# 09_Misc.net
KiCad netlist of a schematic drawn in Altium Designer
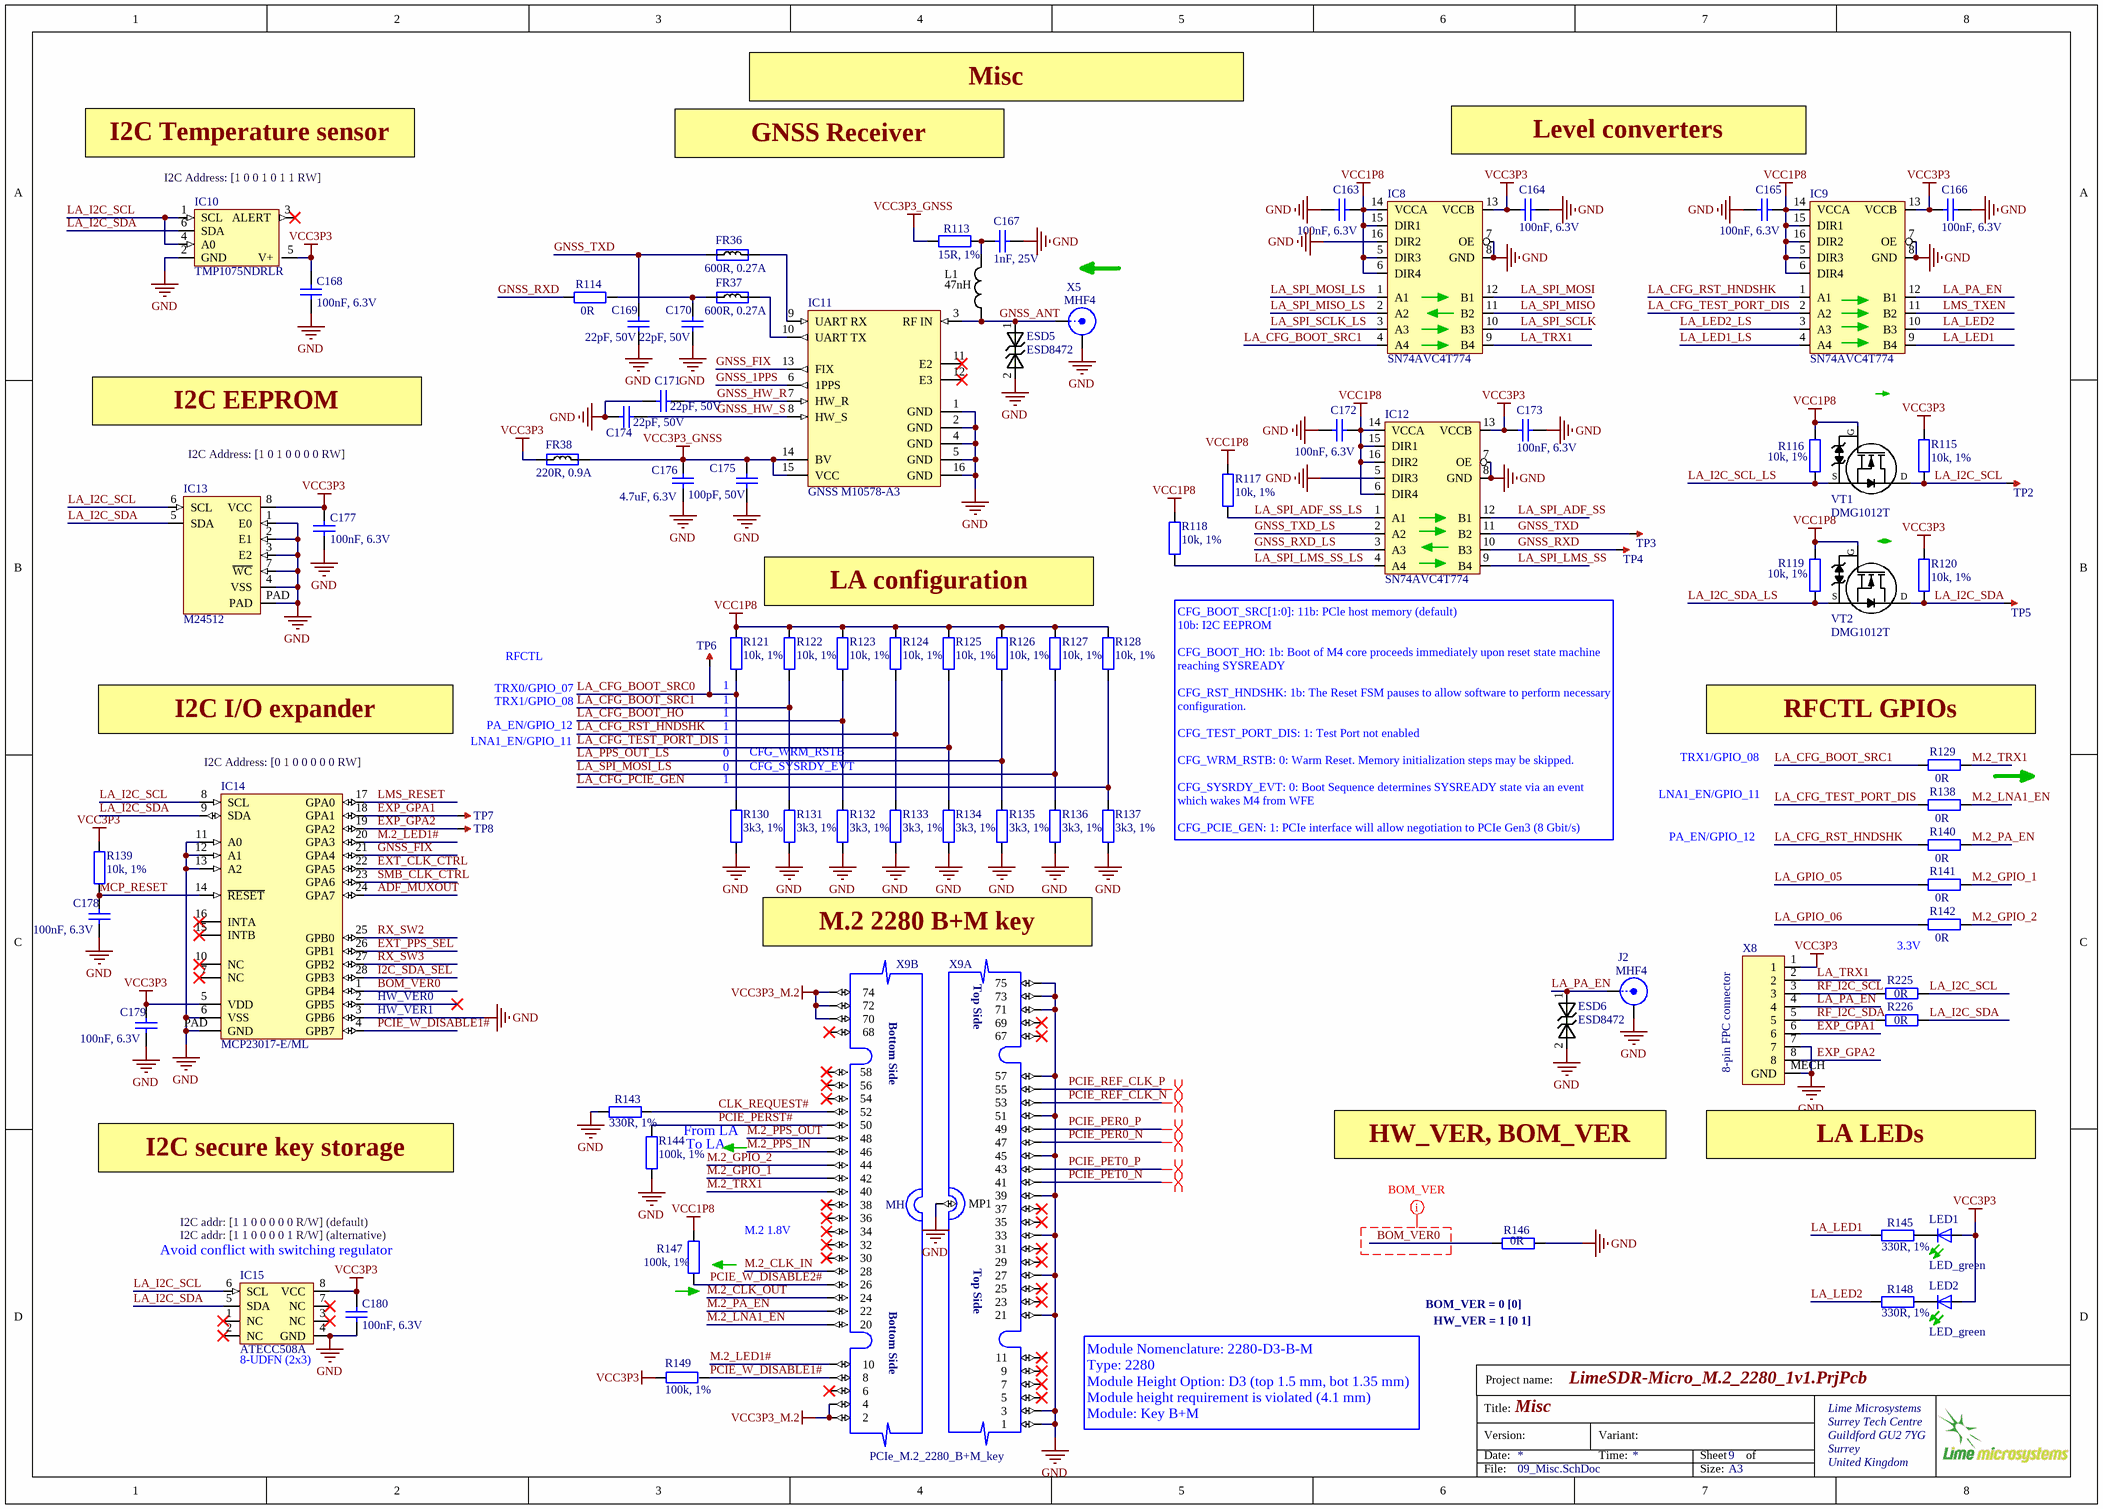
[diagram p0: 09_Misc.SchDoc]

(export (version "E")
  (design (tool "Eeschema 10.0.6"))
  (components
    (comp (ref "C163")
      (value "100nF, 6.3V")
      (footprint "CAP0201")
      (fields (field (name "MANUFACTURER") "Samsung") (field (name "TOLERANCE") "20%"))
      (libsource (lib "LimeMicroAltiumLib_schLib") (part "Cap_0402"))
    )
    (comp (ref "C164")
      (value "100nF, 6.3V")
      (footprint "CAP0201")
      (fields (field (name "MANUFACTURER") "Samsung") (field (name "TOLERANCE") "20%"))
      (libsource (lib "LimeMicroAltiumLib_schLib") (part "Cap_0402"))
    )
    (comp (ref "C165")
      (value "100nF, 6.3V")
      (footprint "CAP0201")
      (fields (field (name "MANUFACTURER") "Samsung") (field (name "TOLERANCE") "20%"))
      (libsource (lib "LimeMicroAltiumLib_schLib") (part "Cap_0402"))
    )
    (comp (ref "C166")
      (value "100nF, 6.3V")
      (footprint "CAP0201")
      (fields (field (name "MANUFACTURER") "Samsung") (field (name "TOLERANCE") "20%"))
      (libsource (lib "LimeMicroAltiumLib_schLib") (part "Cap_0402"))
    )
    (comp (ref "C167")
      (value "1nF, 25V")
      (footprint "CAP0201")
      (fields (field (name "TOLERANCE") "±10%") (field (name "MANUFACTURER") "TDK Corporation"))
      (libsource (lib "LimeMicroAltiumLib_schLib") (part "Cap_0402"))
    )
    (comp (ref "C168")
      (value "100nF, 6.3V")
      (footprint "CAP0201")
      (fields (field (name "MANUFACTURER") "Samsung") (field (name "TOLERANCE") "20%"))
      (libsource (lib "LimeMicroAltiumLib_schLib") (part "Cap_0402"))
    )
    (comp (ref "C169")
      (value "22pF, 50V")
      (footprint "CAP0201")
      (fields
        (field (name "MANUFACTURER") "Murata")
        (field (name "TOLERANCE") "5%")
        (field (name "VOLTAGE") "50V")
      )
      (libsource (lib "LimeMicroAltiumLib_schLib") (part "Cap_0402"))
    )
    (comp (ref "C170")
      (value "22pF, 50V")
      (footprint "CAP0201")
      (fields
        (field (name "MANUFACTURER") "Murata")
        (field (name "TOLERANCE") "5%")
        (field (name "VOLTAGE") "50V")
      )
      (libsource (lib "LimeMicroAltiumLib_schLib") (part "Cap_0402"))
    )
    (comp (ref "C171")
      (value "22pF, 50V")
      (footprint "CAP0201")
      (fields
        (field (name "MANUFACTURER") "Murata")
        (field (name "TOLERANCE") "5%")
        (field (name "VOLTAGE") "50V")
      )
      (libsource (lib "LimeMicroAltiumLib_schLib") (part "Cap_0402"))
    )
    (comp (ref "C172")
      (value "100nF, 6.3V")
      (footprint "CAP0201")
      (fields (field (name "MANUFACTURER") "Samsung") (field (name "TOLERANCE") "20%"))
      (libsource (lib "LimeMicroAltiumLib_schLib") (part "Cap_0402"))
    )
    (comp (ref "C173")
      (value "100nF, 6.3V")
      (footprint "CAP0201")
      (fields (field (name "MANUFACTURER") "Samsung") (field (name "TOLERANCE") "20%"))
      (libsource (lib "LimeMicroAltiumLib_schLib") (part "Cap_0402"))
    )
    (comp (ref "C174")
      (value "22pF, 50V")
      (footprint "CAP0201")
      (fields
        (field (name "MANUFACTURER") "Murata")
        (field (name "TOLERANCE") "5%")
        (field (name "VOLTAGE") "50V")
      )
      (libsource (lib "LimeMicroAltiumLib_schLib") (part "Cap_0402"))
    )
    (comp (ref "C175")
      (value "100pF, 50V")
      (footprint "CAP0201")
      (fields
        (field (name "MANUFACTURER") "TDK")
        (field (name "TOLERANCE") "5%")
        (field (name "VOLTAGE") "50V")
      )
      (libsource (lib "LimeMicroAltiumLib_schLib") (part "Cap_0402"))
    )
    (comp (ref "C176")
      (value "4.7uF, 6.3V")
      (footprint "CAP0402")
      (fields
        (field (name "MANUFACTURER") "Murata Electronics North America")
        (field (name "TOLERANCE") "±20%")
      )
      (libsource (lib "LimeMicroAltiumLib_schLib") (part "Cap_0402"))
    )
    (comp (ref "C177")
      (value "100nF, 6.3V")
      (footprint "CAP0201")
      (fields (field (name "MANUFACTURER") "Samsung") (field (name "TOLERANCE") "20%"))
      (libsource (lib "LimeMicroAltiumLib_schLib") (part "Cap_0402"))
    )
    (comp (ref "C178")
      (value "100nF, 6.3V")
      (footprint "CAP0201")
      (fields (field (name "MANUFACTURER") "Samsung") (field (name "TOLERANCE") "20%"))
      (libsource (lib "LimeMicroAltiumLib_schLib") (part "Cap_0402"))
    )
    (comp (ref "C179")
      (value "100nF, 6.3V")
      (footprint "CAP0201")
      (fields (field (name "MANUFACTURER") "Samsung") (field (name "TOLERANCE") "20%"))
      (libsource (lib "LimeMicroAltiumLib_schLib") (part "Cap_0402"))
    )
    (comp (ref "C180")
      (value "100nF, 6.3V")
      (footprint "CAP0201")
      (fields (field (name "MANUFACTURER") "Samsung") (field (name "TOLERANCE") "20%"))
      (libsource (lib "LimeMicroAltiumLib_schLib") (part "Cap_0402"))
    )
    (comp (ref "ESD5")
      (value "ESD8472")
      (footprint "ESD8472_X3DFN2")
      (fields (field (name "MANUFACTURER") "ON Semiconductor"))
      (libsource (lib "LimeMicroAltiumLib_schLib") (part "ESD8472"))
    )
    (comp (ref "ESD6")
      (value "ESD8472")
      (footprint "ESD8472_X3DFN2")
      (fields (field (name "MANUFACTURER") "ON Semiconductor"))
      (libsource (lib "LimeMicroAltiumLib_schLib") (part "ESD8472"))
    )
    (comp (ref "FR36")
      (value "600R, 0.27A")
      (footprint "RES0201")
      (fields (field (name "MANUFACTURER") "Taiyo Yuden"))
      (libsource (lib "LimeMicroAltiumLib_schLib") (part "Ferrite"))
    )
    (comp (ref "FR37")
      (value "600R, 0.27A")
      (footprint "RES0201")
      (fields (field (name "MANUFACTURER") "Taiyo Yuden"))
      (libsource (lib "LimeMicroAltiumLib_schLib") (part "Ferrite"))
    )
    (comp (ref "FR38")
      (value "220R, 0.9A")
      (footprint "RES0402")
      (fields (field (name "MANUFACTURER") "TDK Corporation"))
      (libsource (lib "LimeFPGAboard_schLib") (part "Ferrite"))
    )
    (comp (ref "IC8")
      (value "SN74AVC4T774")
      (footprint "SN74AVC4T774_v1")
      (fields (field (name "MANUFACTURER") "Texas Instruments"))
      (libsource (lib "LimeMicroAltiumLib") (part "SN74AVC4T774"))
    )
    (comp (ref "IC9")
      (value "SN74AVC4T774")
      (footprint "SN74AVC4T774_v1")
      (fields (field (name "MANUFACTURER") "Texas Instruments"))
      (libsource (lib "LimeMicroAltiumLib") (part "SN74AVC4T774"))
    )
    (comp (ref "IC10")
      (value "TMP1075NDRLR")
      (footprint "TMP1075NDRLR_temperature_sensor_SOT563")
      (fields (field (name "MANUFACTURER") "Texas Instruments"))
      (libsource (lib "LimeMicroAltiumLib_schLib_r04") (part "TMP1075NDRLR_temperature_sensor"))
    )
    (comp (ref "IC11")
      (value "GNSS M10578-A3")
      (footprint "M10578-A3_v2")
      (fields (field (name "MANUFACTURER") "Antenova"))
      (libsource (lib "LimeMicroAltiumLib_schLib_r04") (part "M10578-A3_GPS_GNSS"))
    )
    (comp (ref "IC12")
      (value "SN74AVC4T774")
      (footprint "SN74AVC4T774_v1")
      (fields (field (name "MANUFACTURER") "Texas Instruments"))
      (libsource (lib "LimeMicroAltiumLib") (part "SN74AVC4T774"))
    )
    (comp (ref "IC13")
      (value "M24512")
      (footprint "M24128-DFMC6TG")
      (fields (field (name "MANUFACTURER") "STMicroelectronics"))
      (libsource (lib "LimeMicroAltiumLib_schLib") (part "M24128-DFMC6TG"))
    )
    (comp (ref "IC14")
      (value "MCP23017-E/ML")
      (footprint "MCP23017-E/ML_QFN28")
      (fields (field (name "MANUFACTURER") "Microchip"))
      (libsource (lib "LimeMicroAltiumLib") (part "MCP23017-E/ML_I2C_expander"))
    )
    (comp (ref "IC15")
      (value "ATECC508A")
      (footprint "LimeMicroAltiumLib:ATECC508A_UDFN8_v2")
      (fields (field (name "MANUFACTURER") "Microchip"))
      (libsource (lib "LimeMicroAltiumLib_schLib_r01") (part "ATECC508A_authentication_IC"))
    )
    (comp (ref "J2")
      (value "MHF4")
      (footprint "IPEX_MHF4_conn")
      (description "IPEX MHF4 Connector Jack, Male Pin 50 Ohms Surface Mount Solder")
      (fields (field (name "MANUFACTURER") "TE Connectivity / Linx Technologies"))
      (libsource (lib "LimeMicroAltiumLib_schLib") (part "RF_IF_connector"))
    )
    (comp (ref "L1")
      (value "47nH")
      (footprint "RES0402")
      (fields
        (field (name "MANUFACTURER") "COILCRAFT")
        (field (name "MANUFACTURER PART NUMBER") "0402HP-47NXJLU")
      )
      (libsource (lib "LimeMicroAltiumLib_schLib") (part "Inductor_0603"))
    )
    (comp (ref "LED1")
      (value "LED_green")
      (footprint "LED0201")
      (fields (field (name "MANUFACTURER") "Kingbright"))
      (libsource (lib "LimeFPGAboard_schLib") (part "LED_green"))
    )
    (comp (ref "LED2")
      (value "LED_green")
      (footprint "LED0201")
      (fields (field (name "MANUFACTURER") "Kingbright"))
      (libsource (lib "LimeFPGAboard_schLib") (part "LED_green"))
    )
    (comp (ref "R113")
      (value "15R, 1%")
      (footprint "RES0201")
      (fields (field (name "MANUFACTURER") "Yageo") (field (name "TOLERANCE") "1%"))
      (libsource (lib "LimeFPGAboard_schLib") (part "Res_0402"))
    )
    (comp (ref "R114")
      (value "0R")
      (footprint "RES0201")
      (fields (field (name "MANUFACTURER") "Yageo") (field (name "TOLERANCE") "5%"))
      (libsource (lib "LimeFPGAboard_schLib") (part "Res_0402"))
    )
    (comp (ref "R115")
      (value "10k, 1%")
      (footprint "RES0201")
      (fields (field (name "MANUFACTURER") "Yageo") (field (name "TOLERANCE") "1%"))
      (libsource (lib "LimeFPGAboard_schLib") (part "Res_0402"))
    )
    (comp (ref "R116")
      (value "10k, 1%")
      (footprint "RES0201")
      (fields (field (name "MANUFACTURER") "Yageo") (field (name "TOLERANCE") "1%"))
      (libsource (lib "LimeFPGAboard_schLib") (part "Res_0402"))
    )
    (comp (ref "R117")
      (value "10k, 1%")
      (footprint "RES0201")
      (fields (field (name "MANUFACTURER") "Yageo") (field (name "TOLERANCE") "1%"))
      (libsource (lib "LimeFPGAboard_schLib") (part "Res_0402"))
    )
    (comp (ref "R118")
      (value "10k, 1%")
      (footprint "RES0201")
      (fields (field (name "MANUFACTURER") "Yageo") (field (name "TOLERANCE") "1%"))
      (libsource (lib "LimeFPGAboard_schLib") (part "Res_0402"))
    )
    (comp (ref "R119")
      (value "10k, 1%")
      (footprint "RES0201")
      (fields (field (name "MANUFACTURER") "Yageo") (field (name "TOLERANCE") "1%"))
      (libsource (lib "LimeFPGAboard_schLib") (part "Res_0402"))
    )
    (comp (ref "R120")
      (value "10k, 1%")
      (footprint "RES0201")
      (fields (field (name "MANUFACTURER") "Yageo") (field (name "TOLERANCE") "1%"))
      (libsource (lib "LimeFPGAboard_schLib") (part "Res_0402"))
    )
    (comp (ref "R121")
      (value "10k, 1%")
      (footprint "RES0201")
      (fields (field (name "MANUFACTURER") "Yageo") (field (name "TOLERANCE") "1%"))
      (libsource (lib "LimeFPGAboard_schLib") (part "Res_0402"))
    )
    (comp (ref "R122")
      (value "10k, 1%")
      (footprint "RES0201")
      (fields (field (name "MANUFACTURER") "Yageo") (field (name "TOLERANCE") "1%"))
      (libsource (lib "LimeFPGAboard_schLib") (part "Res_0402"))
    )
    (comp (ref "R123")
      (value "10k, 1%")
      (footprint "RES0201")
      (fields (field (name "MANUFACTURER") "Yageo") (field (name "TOLERANCE") "1%"))
      (libsource (lib "LimeFPGAboard_schLib") (part "Res_0402"))
    )
    (comp (ref "R124")
      (value "10k, 1%")
      (footprint "RES0201")
      (fields (field (name "MANUFACTURER") "Yageo") (field (name "TOLERANCE") "1%"))
      (libsource (lib "LimeFPGAboard_schLib") (part "Res_0402"))
    )
    (comp (ref "R125")
      (value "10k, 1%")
      (footprint "RES0201")
      (fields (field (name "MANUFACTURER") "Yageo") (field (name "TOLERANCE") "1%"))
      (libsource (lib "LimeFPGAboard_schLib") (part "Res_0402"))
    )
    (comp (ref "R126")
      (value "10k, 1%")
      (footprint "RES0201")
      (fields (field (name "MANUFACTURER") "Yageo") (field (name "TOLERANCE") "1%"))
      (libsource (lib "LimeFPGAboard_schLib") (part "Res_0402"))
    )
    (comp (ref "R127")
      (value "10k, 1%")
      (footprint "RES0201")
      (fields (field (name "MANUFACTURER") "Yageo") (field (name "TOLERANCE") "1%"))
      (libsource (lib "LimeFPGAboard_schLib") (part "Res_0402"))
    )
    (comp (ref "R128")
      (value "10k, 1%")
      (footprint "RES0201")
      (fields (field (name "MANUFACTURER") "Yageo") (field (name "TOLERANCE") "1%"))
      (libsource (lib "LimeFPGAboard_schLib") (part "Res_0402"))
    )
    (comp (ref "R129")
      (value "0R")
      (footprint "RES0201")
      (fields (field (name "MANUFACTURER") "Yageo") (field (name "TOLERANCE") "5%"))
      (libsource (lib "LimeFPGAboard_schLib") (part "Res_0402"))
    )
    (comp (ref "R130")
      (value "3k3, 1%")
      (footprint "RES0201")
      (fields (field (name "MANUFACTURER") "Yageo") (field (name "TOLERANCE") "1%"))
      (libsource (lib "LimeFPGAboard_schLib") (part "Res_0402"))
    )
    (comp (ref "R131")
      (value "3k3, 1%")
      (footprint "RES0201")
      (fields (field (name "MANUFACTURER") "Yageo") (field (name "TOLERANCE") "1%"))
      (libsource (lib "LimeFPGAboard_schLib") (part "Res_0402"))
    )
    (comp (ref "R132")
      (value "3k3, 1%")
      (footprint "RES0201")
      (fields (field (name "MANUFACTURER") "Yageo") (field (name "TOLERANCE") "1%"))
      (libsource (lib "LimeFPGAboard_schLib") (part "Res_0402"))
    )
    (comp (ref "R133")
      (value "3k3, 1%")
      (footprint "RES0201")
      (fields (field (name "MANUFACTURER") "Yageo") (field (name "TOLERANCE") "1%"))
      (libsource (lib "LimeFPGAboard_schLib") (part "Res_0402"))
    )
    (comp (ref "R134")
      (value "3k3, 1%")
      (footprint "RES0201")
      (fields (field (name "MANUFACTURER") "Yageo") (field (name "TOLERANCE") "1%"))
      (libsource (lib "LimeFPGAboard_schLib") (part "Res_0402"))
    )
    (comp (ref "R135")
      (value "3k3, 1%")
      (footprint "RES0201")
      (fields (field (name "MANUFACTURER") "Yageo") (field (name "TOLERANCE") "1%"))
      (libsource (lib "LimeFPGAboard_schLib") (part "Res_0402"))
    )
    (comp (ref "R136")
      (value "3k3, 1%")
      (footprint "RES0201")
      (fields (field (name "MANUFACTURER") "Yageo") (field (name "TOLERANCE") "1%"))
      (libsource (lib "LimeFPGAboard_schLib") (part "Res_0402"))
    )
    (comp (ref "R137")
      (value "3k3, 1%")
      (footprint "RES0201")
      (fields (field (name "MANUFACTURER") "Yageo") (field (name "TOLERANCE") "1%"))
      (libsource (lib "LimeFPGAboard_schLib") (part "Res_0402"))
    )
    (comp (ref "R138")
      (value "0R")
      (footprint "RES0201")
      (fields (field (name "MANUFACTURER") "Yageo") (field (name "TOLERANCE") "5%"))
      (libsource (lib "LimeFPGAboard_schLib") (part "Res_0402"))
    )
    (comp (ref "R139")
      (value "10k, 1%")
      (footprint "RES0201")
      (fields (field (name "MANUFACTURER") "Yageo") (field (name "TOLERANCE") "1%"))
      (libsource (lib "LimeFPGAboard_schLib") (part "Res_0402"))
    )
    (comp (ref "R140")
      (value "0R")
      (footprint "RES0201")
      (fields (field (name "MANUFACTURER") "Yageo") (field (name "TOLERANCE") "5%"))
      (libsource (lib "LimeFPGAboard_schLib") (part "Res_0402"))
    )
    (comp (ref "R141")
      (value "0R")
      (footprint "RES0201")
      (fields (field (name "MANUFACTURER") "Yageo") (field (name "TOLERANCE") "5%"))
      (libsource (lib "LimeFPGAboard_schLib") (part "Res_0402"))
    )
    (comp (ref "R142")
      (value "0R")
      (footprint "RES0201")
      (fields (field (name "MANUFACTURER") "Yageo") (field (name "TOLERANCE") "5%"))
      (libsource (lib "LimeFPGAboard_schLib") (part "Res_0402"))
    )
    (comp (ref "R143")
      (value "330R, 1%")
      (footprint "RES0201")
      (fields (field (name "MANUFACTURER") "Vishay Dale") (field (name "TOLERANCE") "1%"))
      (libsource (lib "LimeFPGAboard_schLib") (part "Res_0402"))
    )
    (comp (ref "R144")
      (value "100k, 1%")
      (footprint "RES0201")
      (fields (field (name "MANUFACTURER") "Yageo") (field (name "TOLERANCE") "1%"))
      (libsource (lib "LimeMicroAltiumLib_schLib") (part "Res_0402"))
    )
    (comp (ref "R145")
      (value "330R, 1%")
      (footprint "RES0201")
      (fields (field (name "MANUFACTURER") "Vishay Dale") (field (name "TOLERANCE") "1%"))
      (libsource (lib "LimeFPGAboard_schLib") (part "Res_0402"))
    )
    (comp (ref "R146")
      (value "0R")
      (footprint "RES0201")
      (fields (field (name "MANUFACTURER") "Yageo") (field (name "TOLERANCE") "5%"))
      (libsource (lib "LimeFPGAboard_schLib") (part "Res_0402"))
    )
    (comp (ref "R147")
      (value "100k, 1%")
      (footprint "RES0201")
      (fields (field (name "MANUFACTURER") "Yageo") (field (name "TOLERANCE") "1%"))
      (libsource (lib "LimeMicroAltiumLib_schLib") (part "Res_0402"))
    )
    (comp (ref "R148")
      (value "330R, 1%")
      (footprint "RES0201")
      (fields (field (name "MANUFACTURER") "Vishay Dale") (field (name "TOLERANCE") "1%"))
      (libsource (lib "LimeFPGAboard_schLib") (part "Res_0402"))
    )
    (comp (ref "R149")
      (value "100k, 1%")
      (footprint "RES0201")
      (fields (field (name "MANUFACTURER") "Yageo") (field (name "TOLERANCE") "1%"))
      (libsource (lib "LimeMicroAltiumLib_schLib") (part "Res_0402"))
    )
    (comp (ref "R225")
      (value "0R")
      (footprint "RES0201")
      (fields (field (name "MANUFACTURER") "Yageo") (field (name "TOLERANCE") "5%"))
      (libsource (lib "LimeFPGAboard_schLib") (part "Res_0402"))
    )
    (comp (ref "R226")
      (value "0R")
      (footprint "RES0201")
      (fields (field (name "MANUFACTURER") "Yageo") (field (name "TOLERANCE") "5%"))
      (libsource (lib "LimeFPGAboard_schLib") (part "Res_0402"))
    )
    (comp (ref "TP2")
      (value "TESTPOINT_PAD")
      (footprint "TP_PAD_1MM")
      (description "Test Point PCB mount Miniature White")
      (libsource (lib "LimeMicroAltiumLib_schLib_r04") (part "TESTPOINT_PAD"))
    )
    (comp (ref "TP3")
      (value "TESTPOINT_PAD")
      (footprint "TP_PAD_1MM")
      (description "Test Point PCB mount Miniature White")
      (libsource (lib "LimeMicroAltiumLib_schLib_r04") (part "TESTPOINT_PAD"))
    )
    (comp (ref "TP4")
      (value "TESTPOINT_PAD")
      (footprint "TP_PAD_1MM")
      (description "Test Point PCB mount Miniature White")
      (libsource (lib "LimeMicroAltiumLib_schLib_r04") (part "TESTPOINT_PAD"))
    )
    (comp (ref "TP5")
      (value "TESTPOINT_PAD")
      (footprint "TP_PAD_1MM")
      (description "Test Point PCB mount Miniature White")
      (libsource (lib "LimeMicroAltiumLib_schLib_r04") (part "TESTPOINT_PAD"))
    )
    (comp (ref "TP6")
      (value "TESTPOINT_PAD")
      (footprint "TP_PAD_1MM")
      (description "Test Point PCB mount Miniature White")
      (libsource (lib "LimeMicroAltiumLib_schLib_r04") (part "TESTPOINT_PAD"))
    )
    (comp (ref "TP7")
      (value "TESTPOINT_PAD")
      (footprint "TP_PAD_1MM")
      (description "Test Point PCB mount Miniature White")
      (libsource (lib "LimeMicroAltiumLib_schLib_r04") (part "TESTPOINT_PAD"))
    )
    (comp (ref "TP8")
      (value "TESTPOINT_PAD")
      (footprint "TP_PAD_1MM")
      (description "Test Point PCB mount Miniature White")
      (libsource (lib "LimeMicroAltiumLib_schLib_r04") (part "TESTPOINT_PAD"))
    )
    (comp (ref "VT1")
      (value "DMG1012T")
      (footprint "SOT523")
      (fields (field (name "MANUFACTURER") "Diodes Incorporated"))
      (libsource (lib "LimeMicroAltiumLib_schLib_r01") (part "DMG1012T"))
    )
    (comp (ref "VT2")
      (value "DMG1012T")
      (footprint "SOT523")
      (fields (field (name "MANUFACTURER") "Diodes Incorporated"))
      (libsource (lib "LimeMicroAltiumLib_schLib_r01") (part "DMG1012T"))
    )
    (comp (ref "X5")
      (value "MHF4")
      (footprint "IPEX_MHF4_conn")
      (description "IPEX MHF4 Connector Jack, Male Pin 50 Ohms Surface Mount Solder")
      (fields (field (name "MANUFACTURER") "TE Connectivity / Linx Technologies"))
      (libsource (lib "LimeMicroAltiumLib_schLib") (part "RF_IF_connector"))
    )
    (comp (ref "X8")
      (value "8-pin FPC connector")
      (footprint "503480-0800_8PIN_FPC_CONN")
      (fields (field (name "MANUFACTURER") "Molex"))
      (libsource (lib "LimeMicroAltiumLib_schLib_r04") (part "503480-0800_8PIN_FPC_CONN"))
    )
    (comp (ref "X9")
      (value "PCIe_M.2_2280_B+M_key")
      (footprint "PCIe_M.2_2280_B+M_key")
      (libsource (lib "") (part "PCIe_M.2_2280_B+M_key_1"))
    )
  )
  (nets
    (net (code "1") (name "/ADF_MUXOUT") (class "Default")
      (node (ref "IC14") (pin "24") (pinfunction "GPA7_24") (pintype "bidirectional"))
    )
    (net (code "2") (name "/BOM_VER0") (class "Default")
      (node (ref "IC14") (pin "1") (pinfunction "GPB4_1") (pintype "bidirectional"))
      (node (ref "R146") (pin "1") (pinfunction "1_1") (pintype "passive"))
    )
    (net (code "3") (name "/CLK_REQUEST#") (class "Default")
      (node (ref "R143") (pin "1") (pinfunction "1_1") (pintype "passive"))
      (node (ref "X9") (pin "P52") (pinfunction "52_P52") (pintype "bidirectional"))
    )
    (net (code "4") (name "/EXP_GPA1") (class "Default")
      (node (ref "IC14") (pin "18") (pinfunction "GPA1_18") (pintype "bidirectional"))
      (node (ref "TP7") (pin "1") (pintype "passive"))
      (node (ref "X8") (pin "6") (pinfunction "6_6") (pintype "passive"))
    )
    (net (code "5") (name "/EXP_GPA2") (class "Default")
      (node (ref "IC14") (pin "19") (pinfunction "GPA2_19") (pintype "bidirectional"))
      (node (ref "TP8") (pin "1") (pintype "passive"))
      (node (ref "X8") (pin "8") (pinfunction "8_8") (pintype "passive"))
    )
    (net (code "6") (name "/EXT_CLK_CTRL") (class "Default")
      (node (ref "IC14") (pin "22") (pinfunction "GPA5_22") (pintype "bidirectional"))
    )
    (net (code "7") (name "/EXT_PPS_SEL") (class "Default")
      (node (ref "IC14") (pin "26") (pinfunction "GPB1_26") (pintype "bidirectional"))
    )
    (net (code "8") (name "/GNSS_1PPS") (class "Default")
      (node (ref "IC11") (pin "6") (pinfunction "1PPS_6") (pintype "output"))
    )
    (net (code "9") (name "/GNSS_ANT") (class "Default")
      (node (ref "ESD5") (pin "1") (pinfunction "1_1") (pintype "passive"))
      (node (ref "IC11") (pin "3") (pinfunction "RF_IN_3") (pintype "input"))
      (node (ref "L1") (pin "1") (pinfunction "1_1") (pintype "passive"))
      (node (ref "X5") (pin "1") (pinfunction "X_1") (pintype "passive"))
    )
    (net (code "10") (name "/GNSS_FIX") (class "Default")
      (node (ref "IC11") (pin "13") (pinfunction "FIX_13") (pintype "output"))
      (node (ref "IC14") (pin "21") (pinfunction "GPA4_21") (pintype "bidirectional"))
    )
    (net (code "11") (name "/GNSS_HW_R") (class "Default")
      (node (ref "C171") (pin "1") (pinfunction "1_1") (pintype "passive"))
      (node (ref "IC11") (pin "7") (pinfunction "HW_R_7") (pintype "input"))
    )
    (net (code "12") (name "/GNSS_HW_S") (class "Default")
      (node (ref "C174") (pin "1") (pinfunction "1_1") (pintype "passive"))
      (node (ref "IC11") (pin "8") (pinfunction "HW_S_8") (pintype "input"))
    )
    (net (code "13") (name "/GNSS_RXD") (class "Default")
      (node (ref "IC12") (pin "10") (pinfunction "B3_10") (pintype "passive"))
      (node (ref "R114") (pin "1") (pinfunction "1_1") (pintype "passive"))
      (node (ref "TP4") (pin "1") (pintype "passive"))
    )
    (net (code "14") (name "/GNSS_RXD_LS") (class "Default")
      (node (ref "IC12") (pin "3") (pinfunction "A3_3") (pintype "passive"))
    )
    (net (code "15") (name "/GNSS_TXD") (class "Default")
      (node (ref "C169") (pin "1") (pinfunction "1_1") (pintype "passive"))
      (node (ref "FR36") (pin "1") (pinfunction "1_1") (pintype "passive"))
      (node (ref "IC12") (pin "11") (pinfunction "B2_11") (pintype "passive"))
      (node (ref "TP3") (pin "1") (pintype "passive"))
    )
    (net (code "16") (name "/GNSS_TXD_LS") (class "Default")
      (node (ref "IC12") (pin "2") (pinfunction "A2_2") (pintype "passive"))
    )
    (net (code "17") (name "/I2C_SDA_SEL") (class "Default")
      (node (ref "IC14") (pin "28") (pinfunction "GPB3_28") (pintype "bidirectional"))
    )
    (net (code "18") (name "/LA_CFG_BOOT_HO") (class "Default")
      (node (ref "R123") (pin "2") (pinfunction "2_2") (pintype "passive"))
      (node (ref "R132") (pin "1") (pinfunction "1_1") (pintype "passive"))
    )
    (net (code "19") (name "/LA_CFG_BOOT_SRC0") (class "Default")
      (node (ref "R121") (pin "2") (pinfunction "2_2") (pintype "passive"))
      (node (ref "R130") (pin "1") (pinfunction "1_1") (pintype "passive"))
      (node (ref "TP6") (pin "1") (pintype "passive"))
    )
    (net (code "20") (name "/LA_CFG_BOOT_SRC1") (class "Default")
      (node (ref "IC8") (pin "4") (pinfunction "A4_4") (pintype "passive"))
      (node (ref "R122") (pin "2") (pinfunction "2_2") (pintype "passive"))
      (node (ref "R129") (pin "1") (pinfunction "1_1") (pintype "passive"))
      (node (ref "R131") (pin "1") (pinfunction "1_1") (pintype "passive"))
    )
    (net (code "21") (name "/LA_CFG_PCIE_GEN") (class "Default")
      (node (ref "R128") (pin "2") (pinfunction "2_2") (pintype "passive"))
      (node (ref "R137") (pin "1") (pinfunction "1_1") (pintype "passive"))
    )
    (net (code "22") (name "/LA_CFG_RST_HNDSHK") (class "Default")
      (node (ref "IC9") (pin "1") (pinfunction "A1_1") (pintype "passive"))
      (node (ref "R124") (pin "2") (pinfunction "2_2") (pintype "passive"))
      (node (ref "R133") (pin "1") (pinfunction "1_1") (pintype "passive"))
      (node (ref "R140") (pin "1") (pinfunction "1_1") (pintype "passive"))
    )
    (net (code "23") (name "/LA_CFG_TEST_PORT_DIS") (class "Default")
      (node (ref "IC9") (pin "2") (pinfunction "A2_2") (pintype "passive"))
      (node (ref "R125") (pin "2") (pinfunction "2_2") (pintype "passive"))
      (node (ref "R134") (pin "1") (pinfunction "1_1") (pintype "passive"))
      (node (ref "R138") (pin "1") (pinfunction "1_1") (pintype "passive"))
    )
    (net (code "24") (name "/LA_GPIO_05") (class "Default")
      (node (ref "R141") (pin "1") (pinfunction "1_1") (pintype "passive"))
    )
    (net (code "25") (name "/LA_GPIO_06") (class "Default")
      (node (ref "R142") (pin "1") (pinfunction "1_1") (pintype "passive"))
    )
    (net (code "26") (name "/LA_I2C_SCL") (class "Default")
      (node (ref "IC10") (pin "1") (pinfunction "SCL_1") (pintype "input"))
      (node (ref "IC10") (pin "4") (pinfunction "A0_4") (pintype "input"))
      (node (ref "IC13") (pin "6") (pinfunction "SCL_6") (pintype "input"))
      (node (ref "IC14") (pin "8") (pinfunction "SCL_8") (pintype "input"))
      (node (ref "IC15") (pin "6") (pinfunction "SCL_6") (pintype "input"))
      (node (ref "R115") (pin "2") (pinfunction "2_2") (pintype "passive"))
      (node (ref "R225") (pin "2") (pinfunction "2_2") (pintype "passive"))
      (node (ref "TP2") (pin "1") (pintype "passive"))
      (node (ref "VT1") (pin "D") (pinfunction "D_D") (pintype "passive"))
    )
    (net (code "27") (name "/LA_I2C_SCL_LS") (class "Default")
      (node (ref "R116") (pin "2") (pinfunction "2_2") (pintype "passive"))
      (node (ref "VT1") (pin "S") (pinfunction "S_S") (pintype "passive"))
    )
    (net (code "28") (name "/LA_I2C_SDA") (class "Default")
      (node (ref "IC10") (pin "6") (pinfunction "SDA_6") (pintype "bidirectional"))
      (node (ref "IC13") (pin "5") (pinfunction "SDA_5") (pintype "bidirectional"))
      (node (ref "IC14") (pin "9") (pinfunction "SDA_9") (pintype "bidirectional"))
      (node (ref "IC15") (pin "5") (pinfunction "SDA_5") (pintype "bidirectional"))
      (node (ref "R120") (pin "2") (pinfunction "2_2") (pintype "passive"))
      (node (ref "R226") (pin "2") (pinfunction "2_2") (pintype "passive"))
      (node (ref "TP5") (pin "1") (pintype "passive"))
      (node (ref "VT2") (pin "D") (pinfunction "D_D") (pintype "passive"))
    )
    (net (code "29") (name "/LA_I2C_SDA_LS") (class "Default")
      (node (ref "R119") (pin "2") (pinfunction "2_2") (pintype "passive"))
      (node (ref "VT2") (pin "S") (pinfunction "S_S") (pintype "passive"))
    )
    (net (code "30") (name "/LA_LED1") (class "Default")
      (node (ref "IC9") (pin "9") (pinfunction "B4_9") (pintype "passive"))
      (node (ref "R145") (pin "2") (pinfunction "2_2") (pintype "passive"))
    )
    (net (code "31") (name "/LA_LED1_LS") (class "Default")
      (node (ref "IC9") (pin "4") (pinfunction "A4_4") (pintype "passive"))
    )
    (net (code "32") (name "/LA_LED2") (class "Default")
      (node (ref "IC9") (pin "10") (pinfunction "B3_10") (pintype "passive"))
      (node (ref "R148") (pin "2") (pinfunction "2_2") (pintype "passive"))
    )
    (net (code "33") (name "/LA_LED2_LS") (class "Default")
      (node (ref "IC9") (pin "3") (pinfunction "A3_3") (pintype "passive"))
    )
    (net (code "34") (name "/LA_PA_EN") (class "Default")
      (node (ref "ESD6") (pin "1") (pinfunction "1_1") (pintype "passive"))
      (node (ref "IC9") (pin "12") (pinfunction "B1_12") (pintype "passive"))
      (node (ref "J2") (pin "1") (pinfunction "X_1") (pintype "passive"))
      (node (ref "X8") (pin "4") (pinfunction "4_4") (pintype "passive"))
    )
    (net (code "35") (name "/LA_PPS_OUT_LS") (class "Default")
      (node (ref "R126") (pin "2") (pinfunction "2_2") (pintype "passive"))
      (node (ref "R135") (pin "1") (pinfunction "1_1") (pintype "passive"))
    )
    (net (code "36") (name "/LA_SPI_ADF_SS") (class "Default")
      (node (ref "IC12") (pin "12") (pinfunction "B1_12") (pintype "passive"))
    )
    (net (code "37") (name "/LA_SPI_ADF_SS_LS") (class "Default")
      (node (ref "IC12") (pin "1") (pinfunction "A1_1") (pintype "passive"))
      (node (ref "R117") (pin "2") (pinfunction "2_2") (pintype "passive"))
    )
    (net (code "38") (name "/LA_SPI_LMS_SS") (class "Default")
      (node (ref "IC12") (pin "9") (pinfunction "B4_9") (pintype "passive"))
    )
    (net (code "39") (name "/LA_SPI_LMS_SS_LS") (class "Default")
      (node (ref "IC12") (pin "4") (pinfunction "A4_4") (pintype "passive"))
      (node (ref "R118") (pin "2") (pinfunction "2_2") (pintype "passive"))
    )
    (net (code "40") (name "/LA_SPI_MISO") (class "Default")
      (node (ref "IC8") (pin "11") (pinfunction "B2_11") (pintype "passive"))
    )
    (net (code "41") (name "/LA_SPI_MISO_LS") (class "Default")
      (node (ref "IC8") (pin "2") (pinfunction "A2_2") (pintype "passive"))
    )
    (net (code "42") (name "/LA_SPI_MOSI") (class "Default")
      (node (ref "IC8") (pin "12") (pinfunction "B1_12") (pintype "passive"))
    )
    (net (code "43") (name "/LA_SPI_MOSI_LS") (class "Default")
      (node (ref "IC8") (pin "1") (pinfunction "A1_1") (pintype "passive"))
      (node (ref "R127") (pin "2") (pinfunction "2_2") (pintype "passive"))
      (node (ref "R136") (pin "1") (pinfunction "1_1") (pintype "passive"))
    )
    (net (code "44") (name "/LA_SPI_SCLK") (class "Default")
      (node (ref "IC8") (pin "10") (pinfunction "B3_10") (pintype "passive"))
    )
    (net (code "45") (name "/LA_SPI_SCLK_LS") (class "Default")
      (node (ref "IC8") (pin "3") (pinfunction "A3_3") (pintype "passive"))
    )
    (net (code "46") (name "/LA_TRX1") (class "Default")
      (node (ref "IC8") (pin "9") (pinfunction "B4_9") (pintype "passive"))
      (node (ref "X8") (pin "2") (pinfunction "2_2") (pintype "passive"))
    )
    (net (code "47") (name "/LMS_RESET") (class "Default")
      (node (ref "IC14") (pin "17") (pinfunction "GPA0_17") (pintype "bidirectional"))
    )
    (net (code "48") (name "/LMS_TXEN") (class "Default")
      (node (ref "IC9") (pin "11") (pinfunction "B2_11") (pintype "passive"))
    )
    (net (code "49") (name "/M.2_CLK_IN") (class "Default")
      (node (ref "X9") (pin "P28") (pinfunction "28_P28") (pintype "bidirectional"))
    )
    (net (code "50") (name "/M.2_CLK_OUT") (class "Default")
      (node (ref "X9") (pin "P24") (pinfunction "24_P24") (pintype "bidirectional"))
    )
    (net (code "51") (name "/M.2_GPIO_1") (class "Default")
      (node (ref "R141") (pin "2") (pinfunction "2_2") (pintype "passive"))
      (node (ref "X9") (pin "P42") (pinfunction "42_P42") (pintype "bidirectional"))
    )
    (net (code "52") (name "/M.2_GPIO_2") (class "Default")
      (node (ref "R142") (pin "2") (pinfunction "2_2") (pintype "passive"))
      (node (ref "X9") (pin "P44") (pinfunction "44_P44") (pintype "bidirectional"))
    )
    (net (code "53") (name "/M.2_LED1#") (class "Default")
      (node (ref "IC14") (pin "20") (pinfunction "GPA3_20") (pintype "bidirectional"))
      (node (ref "X9") (pin "P10") (pinfunction "10_P10") (pintype "bidirectional"))
    )
    (net (code "54") (name "/M.2_LNA1_EN") (class "Default")
      (node (ref "R138") (pin "2") (pinfunction "2_2") (pintype "passive"))
      (node (ref "X9") (pin "P20") (pinfunction "20_P20") (pintype "bidirectional"))
    )
    (net (code "55") (name "/M.2_PA_EN") (class "Default")
      (node (ref "R140") (pin "2") (pinfunction "2_2") (pintype "passive"))
      (node (ref "X9") (pin "P22") (pinfunction "22_P22") (pintype "bidirectional"))
    )
    (net (code "56") (name "/M.2_PPS_IN") (class "Default")
      (node (ref "X9") (pin "P46") (pinfunction "46_P46") (pintype "bidirectional"))
    )
    (net (code "57") (name "/M.2_PPS_OUT") (class "Default")
      (node (ref "X9") (pin "P48") (pinfunction "48_P48") (pintype "bidirectional"))
    )
    (net (code "58") (name "/M.2_TRX1") (class "Default")
      (node (ref "R129") (pin "2") (pinfunction "2_2") (pintype "passive"))
      (node (ref "X9") (pin "P40") (pinfunction "40_P40") (pintype "bidirectional"))
    )
    (net (code "59") (name "/MCP_RESET") (class "Default")
      (node (ref "C178") (pin "1") (pinfunction "1_1") (pintype "passive"))
      (node (ref "IC14") (pin "14") (pinfunction "~{RESET}_14") (pintype "input"))
      (node (ref "R139") (pin "2") (pinfunction "2_2") (pintype "passive"))
    )
    (net (code "60") (name "/PCIE_PER0_N") (class "Default")
      (node (ref "X9") (pin "P47") (pinfunction "47_P47") (pintype "bidirectional"))
    )
    (net (code "61") (name "/PCIE_PER0_P") (class "Default")
      (node (ref "X9") (pin "P49") (pinfunction "49_P49") (pintype "bidirectional"))
    )
    (net (code "62") (name "/PCIE_PERST#") (class "Default")
      (node (ref "R144") (pin "2") (pinfunction "2_2") (pintype "passive"))
      (node (ref "X9") (pin "P50") (pinfunction "50_P50") (pintype "bidirectional"))
    )
    (net (code "63") (name "/PCIE_PET0_N") (class "Default")
      (node (ref "X9") (pin "P41") (pinfunction "41_P41") (pintype "bidirectional"))
    )
    (net (code "64") (name "/PCIE_PET0_P") (class "Default")
      (node (ref "X9") (pin "P43") (pinfunction "43_P43") (pintype "bidirectional"))
    )
    (net (code "65") (name "/PCIE_REF_CLK_N") (class "Default")
      (node (ref "X9") (pin "P53") (pinfunction "53_P53") (pintype "bidirectional"))
    )
    (net (code "66") (name "/PCIE_REF_CLK_P") (class "Default")
      (node (ref "X9") (pin "P55") (pinfunction "55_P55") (pintype "bidirectional"))
    )
    (net (code "67") (name "/PCIE_W_DISABLE1#") (class "Default")
      (node (ref "IC14") (pin "4") (pinfunction "GPB7_4") (pintype "bidirectional"))
      (node (ref "R149") (pin "2") (pinfunction "2_2") (pintype "passive"))
      (node (ref "X9") (pin "P8") (pinfunction "8_P8") (pintype "bidirectional"))
    )
    (net (code "68") (name "/PCIE_W_DISABLE2#") (class "Default")
      (node (ref "R147") (pin "2") (pinfunction "2_2") (pintype "passive"))
      (node (ref "X9") (pin "P26") (pinfunction "26_P26") (pintype "bidirectional"))
    )
    (net (code "69") (name "/RF_I2C_SCL") (class "Default")
      (node (ref "R225") (pin "1") (pinfunction "1_1") (pintype "passive"))
      (node (ref "X8") (pin "3") (pinfunction "3_3") (pintype "passive"))
    )
    (net (code "70") (name "/RF_I2C_SDA") (class "Default")
      (node (ref "R226") (pin "1") (pinfunction "1_1") (pintype "passive"))
      (node (ref "X8") (pin "5") (pinfunction "5_5") (pintype "passive"))
    )
    (net (code "71") (name "/RX_SW2") (class "Default")
      (node (ref "IC14") (pin "25") (pinfunction "GPB0_25") (pintype "bidirectional"))
    )
    (net (code "72") (name "/RX_SW3") (class "Default")
      (node (ref "IC14") (pin "27") (pinfunction "GPB2_27") (pintype "bidirectional"))
    )
    (net (code "73") (name "/SMB_CLK_CTRL") (class "Default")
      (node (ref "IC14") (pin "23") (pinfunction "GPA6_23") (pintype "bidirectional"))
    )
    (net (code "74") (name "GND") (class "Default")
      (node (ref "C163") (pin "1") (pinfunction "1_1") (pintype "passive"))
      (node (ref "C164") (pin "2") (pinfunction "2_2") (pintype "passive"))
      (node (ref "C165") (pin "1") (pinfunction "1_1") (pintype "passive"))
      (node (ref "C166") (pin "2") (pinfunction "2_2") (pintype "passive"))
      (node (ref "C167") (pin "2") (pinfunction "2_2") (pintype "passive"))
      (node (ref "C168") (pin "2") (pinfunction "2_2") (pintype "passive"))
      (node (ref "C169") (pin "2") (pinfunction "2_2") (pintype "passive"))
      (node (ref "C170") (pin "2") (pinfunction "2_2") (pintype "passive"))
      (node (ref "C171") (pin "2") (pinfunction "2_2") (pintype "passive"))
      (node (ref "C172") (pin "1") (pinfunction "1_1") (pintype "passive"))
      (node (ref "C173") (pin "2") (pinfunction "2_2") (pintype "passive"))
      (node (ref "C174") (pin "2") (pinfunction "2_2") (pintype "passive"))
      (node (ref "C175") (pin "1") (pinfunction "1_1") (pintype "passive"))
      (node (ref "C176") (pin "1") (pinfunction "1_1") (pintype "passive"))
      (node (ref "C177") (pin "2") (pinfunction "2_2") (pintype "passive"))
      (node (ref "C178") (pin "2") (pinfunction "2_2") (pintype "passive"))
      (node (ref "C179") (pin "2") (pinfunction "2_2") (pintype "passive"))
      (node (ref "C180") (pin "2") (pinfunction "2_2") (pintype "passive"))
      (node (ref "ESD5") (pin "2") (pinfunction "2_2") (pintype "passive"))
      (node (ref "ESD6") (pin "2") (pinfunction "2_2") (pintype "passive"))
      (node (ref "IC10") (pin "2") (pinfunction "GND_2") (pintype "passive"))
      (node (ref "IC11") (pin "1") (pinfunction "GND_1") (pintype "passive"))
      (node (ref "IC11") (pin "16") (pinfunction "GND_16") (pintype "passive"))
      (node (ref "IC11") (pin "2") (pinfunction "GND_2") (pintype "passive"))
      (node (ref "IC11") (pin "4") (pinfunction "GND_4") (pintype "passive"))
      (node (ref "IC11") (pin "5") (pinfunction "GND_5") (pintype "passive"))
      (node (ref "IC12") (pin "5") (pinfunction "DIR3_5") (pintype "passive"))
      (node (ref "IC12") (pin "7") (pinfunction "OE_7") (pintype "passive"))
      (node (ref "IC12") (pin "8") (pinfunction "GND_8") (pintype "passive"))
      (node (ref "IC13") (pin "1") (pinfunction "E0_1") (pintype "input"))
      (node (ref "IC13") (pin "2") (pinfunction "E1_2") (pintype "input"))
      (node (ref "IC13") (pin "3") (pinfunction "E2_3") (pintype "input"))
      (node (ref "IC13") (pin "4") (pinfunction "VSS_4") (pintype "power_in"))
      (node (ref "IC13") (pin "7") (pinfunction "~{WC}_7") (pintype "input"))
      (node (ref "IC13") (pin "PAD") (pinfunction "PAD_PAD") (pintype "power_in"))
      (node (ref "IC14") (pin "11") (pinfunction "A0_11") (pintype "input"))
      (node (ref "IC14") (pin "12") (pinfunction "A1_12") (pintype "input"))
      (node (ref "IC14") (pin "13") (pinfunction "A2_13") (pintype "input"))
      (node (ref "IC14") (pin "3") (pinfunction "GPB6_3") (pintype "bidirectional"))
      (node (ref "IC14") (pin "6") (pinfunction "VSS_6") (pintype "power_in"))
      (node (ref "IC14") (pin "PAD") (pinfunction "GND_PAD") (pintype "passive"))
      (node (ref "IC15") (pin "4") (pinfunction "GND_4") (pintype "passive"))
      (node (ref "IC8") (pin "16") (pinfunction "DIR2_16") (pintype "passive"))
      (node (ref "IC8") (pin "7") (pinfunction "OE_7") (pintype "passive"))
      (node (ref "IC8") (pin "8") (pinfunction "GND_8") (pintype "passive"))
      (node (ref "IC9") (pin "7") (pinfunction "OE_7") (pintype "passive"))
      (node (ref "IC9") (pin "8") (pinfunction "GND_8") (pintype "passive"))
      (node (ref "J2") (pin "2") (pinfunction "Y_2") (pintype "passive"))
      (node (ref "R130") (pin "2") (pinfunction "2_2") (pintype "passive"))
      (node (ref "R131") (pin "2") (pinfunction "2_2") (pintype "passive"))
      (node (ref "R132") (pin "2") (pinfunction "2_2") (pintype "passive"))
      (node (ref "R133") (pin "2") (pinfunction "2_2") (pintype "passive"))
      (node (ref "R134") (pin "2") (pinfunction "2_2") (pintype "passive"))
      (node (ref "R135") (pin "2") (pinfunction "2_2") (pintype "passive"))
      (node (ref "R136") (pin "2") (pinfunction "2_2") (pintype "passive"))
      (node (ref "R137") (pin "2") (pinfunction "2_2") (pintype "passive"))
      (node (ref "R143") (pin "2") (pinfunction "2_2") (pintype "passive"))
      (node (ref "R144") (pin "1") (pinfunction "1_1") (pintype "passive"))
      (node (ref "R146") (pin "2") (pinfunction "2_2") (pintype "passive"))
      (node (ref "X5") (pin "2") (pinfunction "Y_2") (pintype "passive"))
      (node (ref "X8") (pin "7") (pinfunction "7_7") (pintype "passive"))
      (node (ref "X8") (pin "MECH") (pinfunction "GND_MECH") (pintype "passive"))
      (node (ref "X9") (pin "MOUNTING-HOLE") (pinfunction "MP1_MOUNTING-HOLE") (pintype "bidirectional"))
      (node (ref "X9") (pin "P1") (pinfunction "1_P1") (pintype "bidirectional"))
      (node (ref "X9") (pin "P21") (pinfunction "21_P21") (pintype "bidirectional"))
      (node (ref "X9") (pin "P27") (pinfunction "27_P27") (pintype "bidirectional"))
      (node (ref "X9") (pin "P3") (pinfunction "3_P3") (pintype "bidirectional"))
      (node (ref "X9") (pin "P33") (pinfunction "33_P33") (pintype "bidirectional"))
      (node (ref "X9") (pin "P39") (pinfunction "39_P39") (pintype "bidirectional"))
      (node (ref "X9") (pin "P45") (pinfunction "45_P45") (pintype "bidirectional"))
      (node (ref "X9") (pin "P51") (pinfunction "51_P51") (pintype "bidirectional"))
      (node (ref "X9") (pin "P57") (pinfunction "57_P57") (pintype "bidirectional"))
      (node (ref "X9") (pin "P71") (pinfunction "71_P71") (pintype "bidirectional"))
      (node (ref "X9") (pin "P73") (pinfunction "73_P73") (pintype "bidirectional"))
      (node (ref "X9") (pin "P75") (pinfunction "75_P75") (pintype "bidirectional"))
    )
    (net (code "75") (name "Net-(C167-Pad1)") (class "Default")
      (node (ref "C167") (pin "1") (pinfunction "1_1") (pintype "passive"))
      (node (ref "L1") (pin "2") (pinfunction "2_2") (pintype "passive"))
      (node (ref "R113") (pin "1") (pinfunction "1_1") (pintype "passive"))
    )
    (net (code "76") (name "Net-(C170-Pad1)") (class "Default")
      (node (ref "C170") (pin "1") (pinfunction "1_1") (pintype "passive"))
      (node (ref "FR37") (pin "1") (pinfunction "1_1") (pintype "passive"))
      (node (ref "R114") (pin "2") (pinfunction "2_2") (pintype "passive"))
    )
    (net (code "77") (name "Net-(IC11-UART_RX)") (class "Default")
      (node (ref "FR36") (pin "2") (pinfunction "2_2") (pintype "passive"))
      (node (ref "IC11") (pin "9") (pinfunction "UART_RX_9") (pintype "input"))
    )
    (net (code "78") (name "Net-(IC11-UART_TX)") (class "Default")
      (node (ref "FR37") (pin "2") (pinfunction "2_2") (pintype "passive"))
      (node (ref "IC11") (pin "10") (pinfunction "UART_TX_10") (pintype "output"))
    )
    (net (code "79") (name "Net-(LED1-C)") (class "Default")
      (node (ref "LED1") (pin "K") (pinfunction "C_K") (pintype "power_in"))
      (node (ref "R145") (pin "1") (pinfunction "1_1") (pintype "passive"))
    )
    (net (code "80") (name "Net-(LED2-C)") (class "Default")
      (node (ref "LED2") (pin "K") (pinfunction "C_K") (pintype "power_in"))
      (node (ref "R148") (pin "1") (pinfunction "1_1") (pintype "passive"))
    )
    (net (code "81") (name "VCC1P8") (class "Default")
      (node (ref "C163") (pin "2") (pinfunction "2_2") (pintype "passive"))
      (node (ref "C165") (pin "2") (pinfunction "2_2") (pintype "passive"))
      (node (ref "C172") (pin "2") (pinfunction "2_2") (pintype "passive"))
      (node (ref "IC12") (pin "14") (pinfunction "VCCA_14") (pintype "passive"))
      (node (ref "IC12") (pin "15") (pinfunction "DIR1_15") (pintype "passive"))
      (node (ref "IC12") (pin "16") (pinfunction "DIR2_16") (pintype "passive"))
      (node (ref "IC12") (pin "6") (pinfunction "DIR4_6") (pintype "passive"))
      (node (ref "IC8") (pin "14") (pinfunction "VCCA_14") (pintype "passive"))
      (node (ref "IC8") (pin "15") (pinfunction "DIR1_15") (pintype "passive"))
      (node (ref "IC8") (pin "5") (pinfunction "DIR3_5") (pintype "passive"))
      (node (ref "IC8") (pin "6") (pinfunction "DIR4_6") (pintype "passive"))
      (node (ref "IC9") (pin "14") (pinfunction "VCCA_14") (pintype "passive"))
      (node (ref "IC9") (pin "15") (pinfunction "DIR1_15") (pintype "passive"))
      (node (ref "IC9") (pin "16") (pinfunction "DIR2_16") (pintype "passive"))
      (node (ref "IC9") (pin "5") (pinfunction "DIR3_5") (pintype "passive"))
      (node (ref "IC9") (pin "6") (pinfunction "DIR4_6") (pintype "passive"))
      (node (ref "R116") (pin "1") (pinfunction "1_1") (pintype "passive"))
      (node (ref "R117") (pin "1") (pinfunction "1_1") (pintype "passive"))
      (node (ref "R118") (pin "1") (pinfunction "1_1") (pintype "passive"))
      (node (ref "R119") (pin "1") (pinfunction "1_1") (pintype "passive"))
      (node (ref "R121") (pin "1") (pinfunction "1_1") (pintype "passive"))
      (node (ref "R122") (pin "1") (pinfunction "1_1") (pintype "passive"))
      (node (ref "R123") (pin "1") (pinfunction "1_1") (pintype "passive"))
      (node (ref "R124") (pin "1") (pinfunction "1_1") (pintype "passive"))
      (node (ref "R125") (pin "1") (pinfunction "1_1") (pintype "passive"))
      (node (ref "R126") (pin "1") (pinfunction "1_1") (pintype "passive"))
      (node (ref "R127") (pin "1") (pinfunction "1_1") (pintype "passive"))
      (node (ref "R128") (pin "1") (pinfunction "1_1") (pintype "passive"))
      (node (ref "R147") (pin "1") (pinfunction "1_1") (pintype "passive"))
      (node (ref "VT1") (pin "G") (pinfunction "G_G") (pintype "passive"))
      (node (ref "VT2") (pin "G") (pinfunction "G_G") (pintype "passive"))
    )
    (net (code "82") (name "VCC3P3") (class "Default")
      (node (ref "C164") (pin "1") (pinfunction "1_1") (pintype "passive"))
      (node (ref "C166") (pin "1") (pinfunction "1_1") (pintype "passive"))
      (node (ref "C168") (pin "1") (pinfunction "1_1") (pintype "passive"))
      (node (ref "C173") (pin "1") (pinfunction "1_1") (pintype "passive"))
      (node (ref "C177") (pin "1") (pinfunction "1_1") (pintype "passive"))
      (node (ref "C179") (pin "1") (pinfunction "1_1") (pintype "passive"))
      (node (ref "C180") (pin "1") (pinfunction "1_1") (pintype "passive"))
      (node (ref "FR38") (pin "1") (pinfunction "1_1") (pintype "passive"))
      (node (ref "IC10") (pin "5") (pinfunction "V+_5") (pintype "power_in"))
      (node (ref "IC12") (pin "13") (pinfunction "VCCB_13") (pintype "passive"))
      (node (ref "IC13") (pin "8") (pinfunction "VCC_8") (pintype "power_in"))
      (node (ref "IC14") (pin "5") (pinfunction "VDD_5") (pintype "power_in"))
      (node (ref "IC15") (pin "8") (pinfunction "VCC_8") (pintype "power_in"))
      (node (ref "IC8") (pin "13") (pinfunction "VCCB_13") (pintype "passive"))
      (node (ref "IC9") (pin "13") (pinfunction "VCCB_13") (pintype "passive"))
      (node (ref "LED1") (pin "A") (pinfunction "A_A") (pintype "power_in"))
      (node (ref "LED2") (pin "A") (pinfunction "A_A") (pintype "power_in"))
      (node (ref "R115") (pin "1") (pinfunction "1_1") (pintype "passive"))
      (node (ref "R120") (pin "1") (pinfunction "1_1") (pintype "passive"))
      (node (ref "R139") (pin "1") (pinfunction "1_1") (pintype "passive"))
      (node (ref "R149") (pin "1") (pinfunction "1_1") (pintype "passive"))
      (node (ref "X8") (pin "1") (pinfunction "1_1") (pintype "passive"))
    )
    (net (code "83") (name "VCC3P3_GNSS") (class "Default")
      (node (ref "C175") (pin "2") (pinfunction "2_2") (pintype "passive"))
      (node (ref "C176") (pin "2") (pinfunction "2_2") (pintype "passive"))
      (node (ref "FR38") (pin "2") (pinfunction "2_2") (pintype "passive"))
      (node (ref "IC11") (pin "14") (pinfunction "BV_14") (pintype "power_in"))
      (node (ref "IC11") (pin "15") (pinfunction "VCC_15") (pintype "power_in"))
      (node (ref "R113") (pin "2") (pinfunction "2_2") (pintype "passive"))
    )
    (net (code "84") (name "VCC3P3_M.2") (class "Default")
      (node (ref "X9") (pin "P2") (pinfunction "2_P2") (pintype "bidirectional"))
      (node (ref "X9") (pin "P4") (pinfunction "4_P4") (pintype "bidirectional"))
      (node (ref "X9") (pin "P70") (pinfunction "70_P70") (pintype "bidirectional"))
      (node (ref "X9") (pin "P72") (pinfunction "72_P72") (pintype "bidirectional"))
      (node (ref "X9") (pin "P74") (pinfunction "74_P74") (pintype "bidirectional"))
    )
    (net (code "85") (name "unconnected-(IC10-ALERT-Pad3)") (class "Default")
      (node (ref "IC10") (pin "3") (pinfunction "ALERT_3") (pintype "output+no_connect"))
    )
    (net (code "86") (name "unconnected-(IC11-E2-Pad11)") (class "Default")
      (node (ref "IC11") (pin "11") (pinfunction "E2_11") (pintype "passive+no_connect"))
    )
    (net (code "87") (name "unconnected-(IC11-E3-Pad12)") (class "Default")
      (node (ref "IC11") (pin "12") (pinfunction "E3_12") (pintype "passive+no_connect"))
    )
    (net (code "88") (name "unconnected-(IC14-GPB5-Pad2)") (class "Default")
      (node (ref "IC14") (pin "2") (pinfunction "GPB5_2") (pintype "bidirectional+no_connect"))
    )
    (net (code "89") (name "unconnected-(IC14-INTA-Pad16)") (class "Default")
      (node (ref "IC14") (pin "16") (pinfunction "INTA_16") (pintype "open_collector+no_connect"))
    )
    (net (code "90") (name "unconnected-(IC14-INTB-Pad15)") (class "Default")
      (node (ref "IC14") (pin "15") (pinfunction "INTB_15") (pintype "open_collector+no_connect"))
    )
    (net (code "91") (name "unconnected-(IC14-NC-Pad7)") (class "Default")
      (node (ref "IC14") (pin "7") (pinfunction "NC_7") (pintype "passive+no_connect"))
    )
    (net (code "92") (name "unconnected-(IC14-NC-Pad10)") (class "Default")
      (node (ref "IC14") (pin "10") (pinfunction "NC_10") (pintype "passive+no_connect"))
    )
    (net (code "93") (name "unconnected-(IC15-NC-Pad1)") (class "Default")
      (node (ref "IC15") (pin "1") (pinfunction "NC_1") (pintype "passive+no_connect"))
    )
    (net (code "94") (name "unconnected-(IC15-NC-Pad2)") (class "Default")
      (node (ref "IC15") (pin "2") (pinfunction "NC_2") (pintype "passive+no_connect"))
    )
    (net (code "95") (name "unconnected-(IC15-NC-Pad3)") (class "Default")
      (node (ref "IC15") (pin "3") (pinfunction "NC_3") (pintype "passive+no_connect"))
    )
    (net (code "96") (name "unconnected-(IC15-NC-Pad7)") (class "Default")
      (node (ref "IC15") (pin "7") (pinfunction "NC_7") (pintype "passive+no_connect"))
    )
    (net (code "97") (name "unconnected-(X9A-5-PadP5)") (class "Default")
      (node (ref "X9") (pin "P5") (pinfunction "5_P5") (pintype "bidirectional+no_connect"))
    )
    (net (code "98") (name "unconnected-(X9A-7-PadP7)") (class "Default")
      (node (ref "X9") (pin "P7") (pinfunction "7_P7") (pintype "bidirectional+no_connect"))
    )
    (net (code "99") (name "unconnected-(X9A-9-PadP9)") (class "Default")
      (node (ref "X9") (pin "P9") (pinfunction "9_P9") (pintype "bidirectional+no_connect"))
    )
    (net (code "100") (name "unconnected-(X9A-11-PadP11)") (class "Default")
      (node (ref "X9") (pin "P11") (pinfunction "11_P11") (pintype "bidirectional+no_connect"))
    )
    (net (code "101") (name "unconnected-(X9A-23-PadP23)") (class "Default")
      (node (ref "X9") (pin "P23") (pinfunction "23_P23") (pintype "bidirectional+no_connect"))
    )
    (net (code "102") (name "unconnected-(X9A-25-PadP25)") (class "Default")
      (node (ref "X9") (pin "P25") (pinfunction "25_P25") (pintype "bidirectional+no_connect"))
    )
    (net (code "103") (name "unconnected-(X9A-29-PadP29)") (class "Default")
      (node (ref "X9") (pin "P29") (pinfunction "29_P29") (pintype "bidirectional+no_connect"))
    )
    (net (code "104") (name "unconnected-(X9A-31-PadP31)") (class "Default")
      (node (ref "X9") (pin "P31") (pinfunction "31_P31") (pintype "bidirectional+no_connect"))
    )
    (net (code "105") (name "unconnected-(X9A-35-PadP35)") (class "Default")
      (node (ref "X9") (pin "P35") (pinfunction "35_P35") (pintype "bidirectional+no_connect"))
    )
    (net (code "106") (name "unconnected-(X9A-37-PadP37)") (class "Default")
      (node (ref "X9") (pin "P37") (pinfunction "37_P37") (pintype "bidirectional+no_connect"))
    )
    (net (code "107") (name "unconnected-(X9A-67-PadP67)") (class "Default")
      (node (ref "X9") (pin "P67") (pinfunction "67_P67") (pintype "bidirectional+no_connect"))
    )
    (net (code "108") (name "unconnected-(X9A-69-PadP69)") (class "Default")
      (node (ref "X9") (pin "P69") (pinfunction "69_P69") (pintype "bidirectional+no_connect"))
    )
    (net (code "109") (name "unconnected-(X9B-6-PadP6)") (class "Default")
      (node (ref "X9") (pin "P6") (pinfunction "6_P6") (pintype "bidirectional+no_connect"))
    )
    (net (code "110") (name "unconnected-(X9B-30-PadP30)") (class "Default")
      (node (ref "X9") (pin "P30") (pinfunction "30_P30") (pintype "bidirectional+no_connect"))
    )
    (net (code "111") (name "unconnected-(X9B-32-PadP32)") (class "Default")
      (node (ref "X9") (pin "P32") (pinfunction "32_P32") (pintype "bidirectional+no_connect"))
    )
    (net (code "112") (name "unconnected-(X9B-34-PadP34)") (class "Default")
      (node (ref "X9") (pin "P34") (pinfunction "34_P34") (pintype "bidirectional+no_connect"))
    )
    (net (code "113") (name "unconnected-(X9B-36-PadP36)") (class "Default")
      (node (ref "X9") (pin "P36") (pinfunction "36_P36") (pintype "bidirectional+no_connect"))
    )
    (net (code "114") (name "unconnected-(X9B-38-PadP38)") (class "Default")
      (node (ref "X9") (pin "P38") (pinfunction "38_P38") (pintype "bidirectional+no_connect"))
    )
    (net (code "115") (name "unconnected-(X9B-54-PadP54)") (class "Default")
      (node (ref "X9") (pin "P54") (pinfunction "54_P54") (pintype "bidirectional+no_connect"))
    )
    (net (code "116") (name "unconnected-(X9B-56-PadP56)") (class "Default")
      (node (ref "X9") (pin "P56") (pinfunction "56_P56") (pintype "bidirectional+no_connect"))
    )
    (net (code "117") (name "unconnected-(X9B-58-PadP58)") (class "Default")
      (node (ref "X9") (pin "P58") (pinfunction "58_P58") (pintype "bidirectional+no_connect"))
    )
    (net (code "118") (name "unconnected-(X9B-68-PadP68)") (class "Default")
      (node (ref "X9") (pin "P68") (pinfunction "68_P68") (pintype "bidirectional+no_connect"))
    )
  )
)
